# MS_8ADCPWM.net
KiCad netlist of a schematic drawn in EAGLE
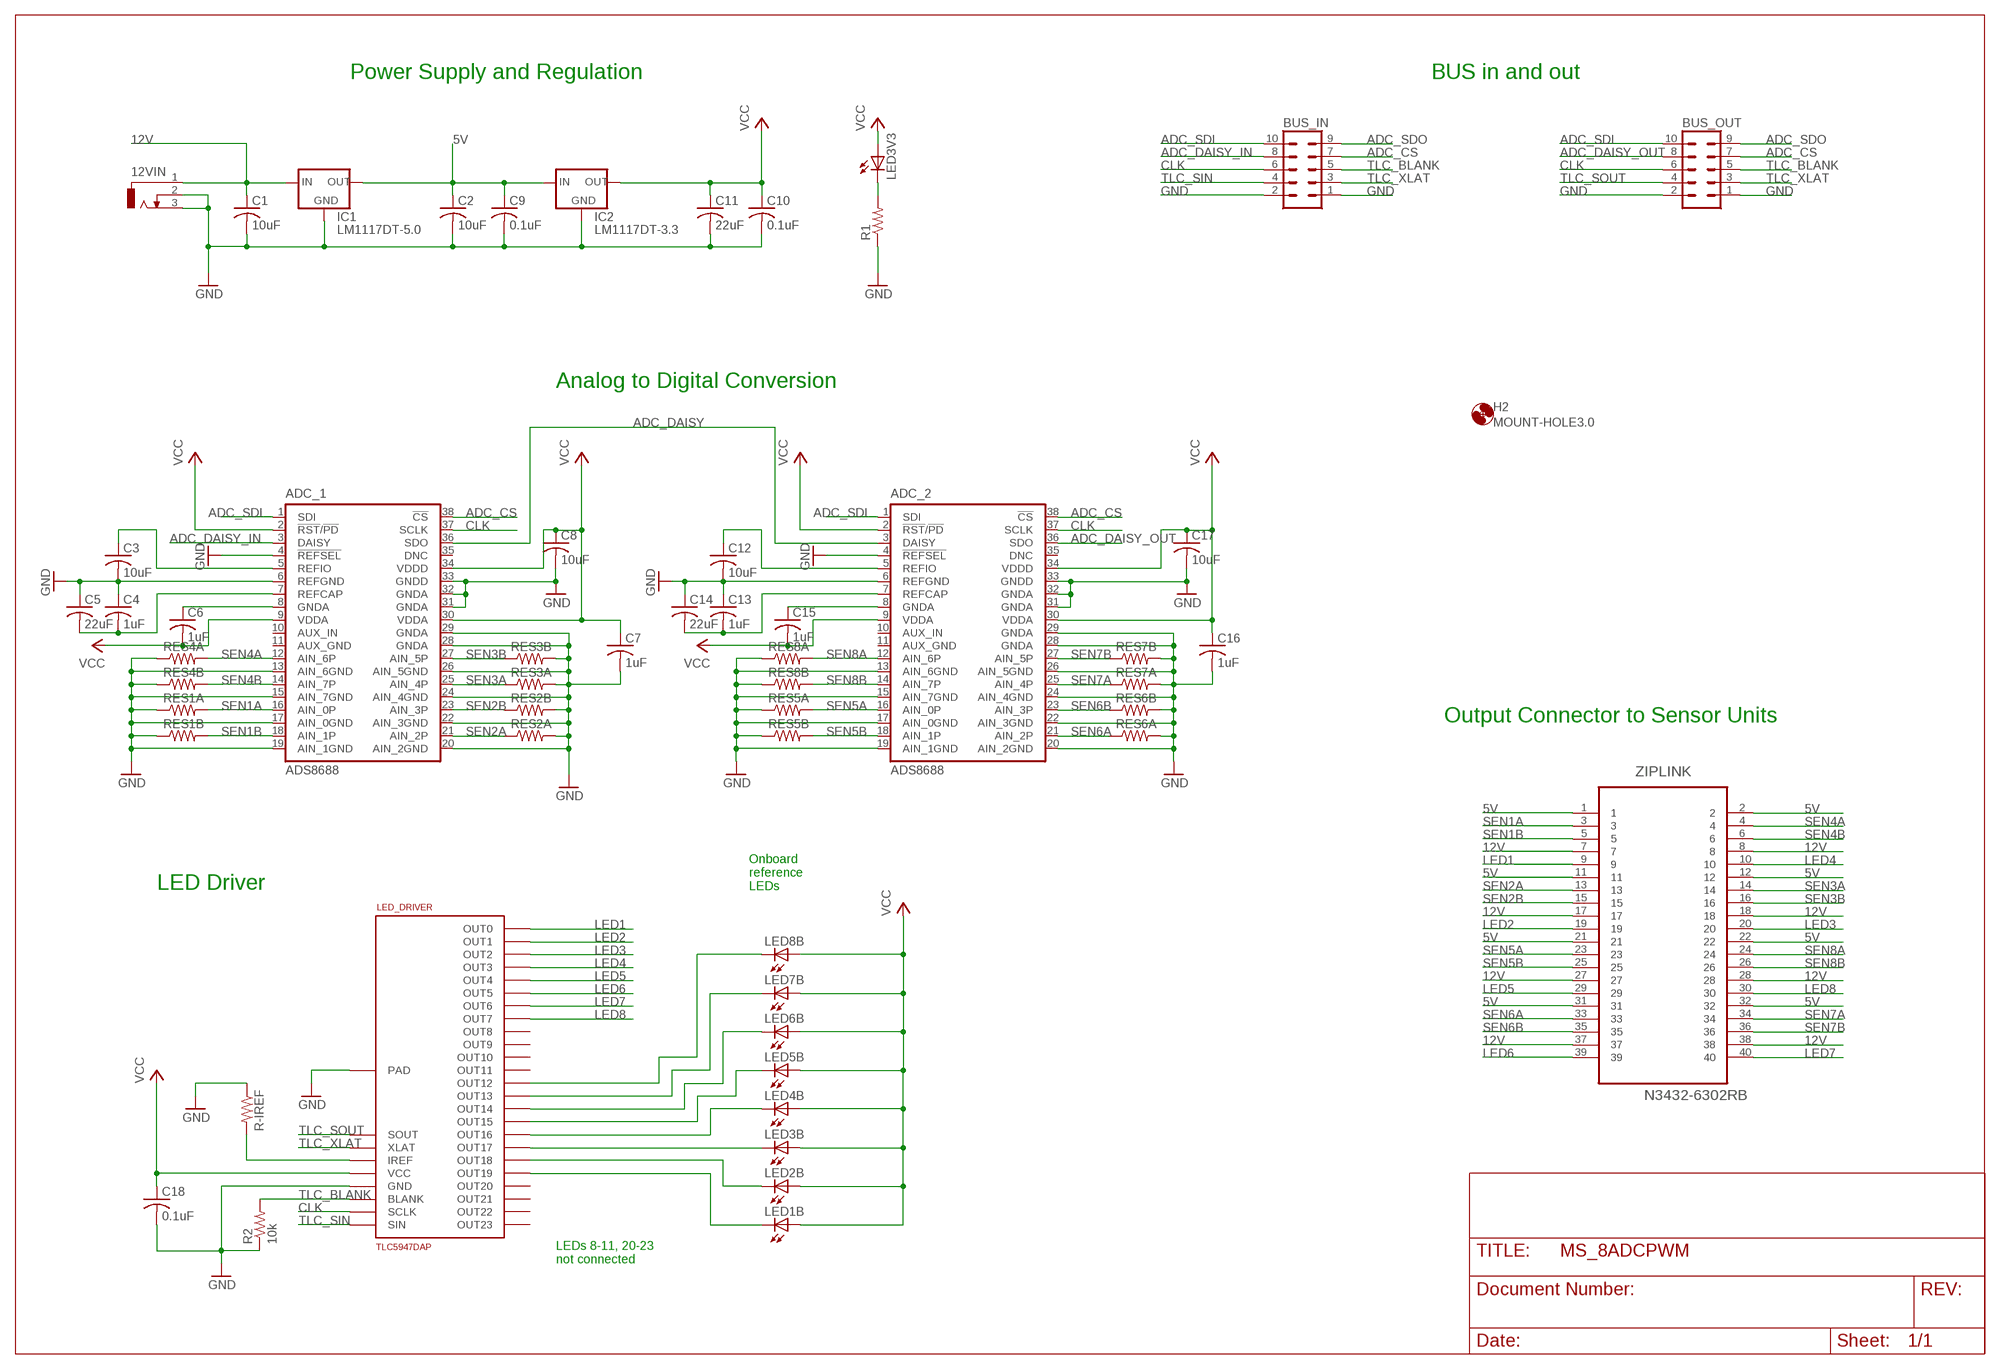
[diagram p0: schematic, sheet 1]

(export (version "E")
  (design (tool "Eeschema 10.0.6"))
  (components
    (comp (ref "12VIN")
      (value "DCJ0303")
      (footprint "eagle-import:DCJ0303")
      (libsource (lib "eagle-import") (part "DCJ0303"))
    )
    (comp (ref "ADC_1")
      (value "ADS8688")
      (footprint "eagle-import:DBT_R-PDSO-G38")
      (libsource (lib "eagle-import") (part "ADS8688"))
    )
    (comp (ref "ADC_2")
      (value "ADS8688")
      (footprint "eagle-import:DBT_R-PDSO-G38")
      (libsource (lib "eagle-import") (part "ADS8688"))
    )
    (comp (ref "BUS_IN")
      (value "ML10")
      (footprint "eagle-import:ML10")
      (libsource (lib "eagle-import") (part "ML10"))
    )
    (comp (ref "BUS_OUT")
      (value "ML10")
      (footprint "eagle-import:ML10")
      (libsource (lib "eagle-import") (part "ML10"))
    )
    (comp (ref "C1")
      (value "10uF")
      (footprint "eagle-import:C0805")
      (libsource (lib "eagle-import") (part "C-USC0805"))
    )
    (comp (ref "C2")
      (value "10uF")
      (footprint "eagle-import:C0805")
      (libsource (lib "eagle-import") (part "C-USC0805"))
    )
    (comp (ref "C3")
      (value "10uF")
      (footprint "eagle-import:C0805")
      (libsource (lib "eagle-import") (part "C-USC0805"))
    )
    (comp (ref "C4")
      (value "1uF")
      (footprint "eagle-import:C0805")
      (libsource (lib "eagle-import") (part "C-USC0805"))
    )
    (comp (ref "C5")
      (value "22uF")
      (footprint "eagle-import:C0805")
      (libsource (lib "eagle-import") (part "C-USC0805"))
    )
    (comp (ref "C6")
      (value "1uF")
      (footprint "eagle-import:C0805")
      (libsource (lib "eagle-import") (part "C-USC0805"))
    )
    (comp (ref "C7")
      (value "1uF")
      (footprint "eagle-import:C0805")
      (libsource (lib "eagle-import") (part "C-USC0805"))
    )
    (comp (ref "C8")
      (value "10uF")
      (footprint "eagle-import:C0805")
      (libsource (lib "eagle-import") (part "C-USC0805"))
    )
    (comp (ref "C9")
      (value "0.1uF")
      (footprint "eagle-import:C0805")
      (libsource (lib "eagle-import") (part "C-USC0805"))
    )
    (comp (ref "C10")
      (value "0.1uF")
      (footprint "eagle-import:C0805")
      (libsource (lib "eagle-import") (part "C-USC0805"))
    )
    (comp (ref "C11")
      (value "22uF")
      (footprint "eagle-import:C0805")
      (libsource (lib "eagle-import") (part "C-USC0805"))
    )
    (comp (ref "C12")
      (value "10uF")
      (footprint "eagle-import:C0805")
      (libsource (lib "eagle-import") (part "C-USC0805"))
    )
    (comp (ref "C13")
      (value "1uF")
      (footprint "eagle-import:C0805")
      (libsource (lib "eagle-import") (part "C-USC0805"))
    )
    (comp (ref "C14")
      (value "22uF")
      (footprint "eagle-import:C0805")
      (libsource (lib "eagle-import") (part "C-USC0805"))
    )
    (comp (ref "C15")
      (value "1uF")
      (footprint "eagle-import:C0805")
      (libsource (lib "eagle-import") (part "C-USC0805"))
    )
    (comp (ref "C16")
      (value "1uF")
      (footprint "eagle-import:C0805")
      (libsource (lib "eagle-import") (part "C-USC0805"))
    )
    (comp (ref "C17")
      (value "10uF")
      (footprint "eagle-import:C0805")
      (libsource (lib "eagle-import") (part "C-USC0805"))
    )
    (comp (ref "C18")
      (value "0.1uF")
      (footprint "eagle-import:C0805")
      (libsource (lib "eagle-import") (part "C-USC0805"))
    )
    (comp (ref "H2")
      (value "MOUNT-HOLE3.0")
      (footprint "eagle-import:3,0")
      (libsource (lib "eagle-import") (part "MOUNT-HOLE3.0"))
    )
    (comp (ref "IC1")
      (value "LM1117DT-5.0")
      (footprint "eagle-import:TO252")
      (fields (field (name "MF") "Texas Instruments"))
      (libsource (lib "eagle-import") (part "LM1117?-DT5.0"))
    )
    (comp (ref "IC2")
      (value "LM1117DT-3.3")
      (footprint "eagle-import:TO252")
      (fields (field (name "MF") "Texas Instruments"))
      (libsource (lib "eagle-import") (part "LM1117?-DT3.3"))
    )
    (comp (ref "LED1B")
      (value "LEDSMD2PLCC")
      (footprint "eagle-import:2-PLCC")
      (libsource (lib "eagle-import") (part "LEDSMD2PLCC"))
    )
    (comp (ref "LED2B")
      (value "LEDSMD2PLCC")
      (footprint "eagle-import:2-PLCC")
      (libsource (lib "eagle-import") (part "LEDSMD2PLCC"))
    )
    (comp (ref "LED3B")
      (value "LEDSMD2PLCC")
      (footprint "eagle-import:2-PLCC")
      (libsource (lib "eagle-import") (part "LEDSMD2PLCC"))
    )
    (comp (ref "LED3V3")
      (value "LEDCHIPLED_0805")
      (footprint "eagle-import:CHIPLED_0805")
      (libsource (lib "eagle-import") (part "LEDCHIPLED_0805"))
    )
    (comp (ref "LED4B")
      (value "LEDSMD2PLCC")
      (footprint "eagle-import:2-PLCC")
      (libsource (lib "eagle-import") (part "LEDSMD2PLCC"))
    )
    (comp (ref "LED5B")
      (value "LEDSMD2PLCC")
      (footprint "eagle-import:2-PLCC")
      (libsource (lib "eagle-import") (part "LEDSMD2PLCC"))
    )
    (comp (ref "LED6B")
      (value "LEDSMD2PLCC")
      (footprint "eagle-import:2-PLCC")
      (libsource (lib "eagle-import") (part "LEDSMD2PLCC"))
    )
    (comp (ref "LED7B")
      (value "LEDSMD2PLCC")
      (footprint "eagle-import:2-PLCC")
      (libsource (lib "eagle-import") (part "LEDSMD2PLCC"))
    )
    (comp (ref "LED8B")
      (value "LEDSMD2PLCC")
      (footprint "eagle-import:2-PLCC")
      (libsource (lib "eagle-import") (part "LEDSMD2PLCC"))
    )
    (comp (ref "LED_DRIVER")
      (value "TLC5947DAP")
      (footprint "eagle-import:HTSSOP32DAP")
      (libsource (lib "eagle-import") (part "TLC5947DAP"))
    )
    (comp (ref "R-IREF")
      (value "R-US_R1206")
      (footprint "eagle-import:R1206")
      (libsource (lib "eagle-import") (part "R-US_R1206"))
    )
    (comp (ref "R1")
      (value "R-US_R0805")
      (footprint "eagle-import:R0805")
      (libsource (lib "eagle-import") (part "R-US_R0805"))
    )
    (comp (ref "R2")
      (value "10k")
      (footprint "eagle-import:R1206")
      (libsource (lib "eagle-import") (part "R-US_R1206"))
    )
    (comp (ref "RES1A")
      (value "R-US_R1206")
      (footprint "eagle-import:R1206")
      (libsource (lib "eagle-import") (part "R-US_R1206"))
    )
    (comp (ref "RES1B")
      (value "R-US_R1206")
      (footprint "eagle-import:R1206")
      (libsource (lib "eagle-import") (part "R-US_R1206"))
    )
    (comp (ref "RES2A")
      (value "R-US_R1206")
      (footprint "eagle-import:R1206")
      (libsource (lib "eagle-import") (part "R-US_R1206"))
    )
    (comp (ref "RES2B")
      (value "R-US_R1206")
      (footprint "eagle-import:R1206")
      (libsource (lib "eagle-import") (part "R-US_R1206"))
    )
    (comp (ref "RES3A")
      (value "R-US_R1206")
      (footprint "eagle-import:R1206")
      (libsource (lib "eagle-import") (part "R-US_R1206"))
    )
    (comp (ref "RES3B")
      (value "R-US_R1206")
      (footprint "eagle-import:R1206")
      (libsource (lib "eagle-import") (part "R-US_R1206"))
    )
    (comp (ref "RES4A")
      (value "R-US_R1206")
      (footprint "eagle-import:R1206")
      (libsource (lib "eagle-import") (part "R-US_R1206"))
    )
    (comp (ref "RES4B")
      (value "R-US_R1206")
      (footprint "eagle-import:R1206")
      (libsource (lib "eagle-import") (part "R-US_R1206"))
    )
    (comp (ref "RES5A")
      (value "R-US_R1206")
      (footprint "eagle-import:R1206")
      (libsource (lib "eagle-import") (part "R-US_R1206"))
    )
    (comp (ref "RES5B")
      (value "R-US_R1206")
      (footprint "eagle-import:R1206")
      (libsource (lib "eagle-import") (part "R-US_R1206"))
    )
    (comp (ref "RES6A")
      (value "R-US_R1206")
      (footprint "eagle-import:R1206")
      (libsource (lib "eagle-import") (part "R-US_R1206"))
    )
    (comp (ref "RES6B")
      (value "R-US_R1206")
      (footprint "eagle-import:R1206")
      (libsource (lib "eagle-import") (part "R-US_R1206"))
    )
    (comp (ref "RES7A")
      (value "R-US_R1206")
      (footprint "eagle-import:R1206")
      (libsource (lib "eagle-import") (part "R-US_R1206"))
    )
    (comp (ref "RES7B")
      (value "R-US_R1206")
      (footprint "eagle-import:R1206")
      (libsource (lib "eagle-import") (part "R-US_R1206"))
    )
    (comp (ref "RES8A")
      (value "R-US_R1206")
      (footprint "eagle-import:R1206")
      (libsource (lib "eagle-import") (part "R-US_R1206"))
    )
    (comp (ref "RES8B")
      (value "R-US_R1206")
      (footprint "eagle-import:R1206")
      (libsource (lib "eagle-import") (part "R-US_R1206"))
    )
    (comp (ref "ZIPLINK")
      (value "N3432-6302RB")
      (footprint "eagle-import:3M_N3432-6302RB")
      (fields (field (name "MF") "3M"))
      (libsource (lib "eagle-import") (part "N3432-6302RB"))
    )
  )
  (nets
    (net (code "1") (name "/5V") (class "Default")
      (node (ref "C2") (pin "1") (pinfunction "1_1") (pintype "passive"))
      (node (ref "C9") (pin "1") (pinfunction "1_1") (pintype "passive"))
      (node (ref "IC1") (pin "3") (pinfunction "OUT_3") (pintype "passive"))
      (node (ref "IC2") (pin "2") (pinfunction "IN_2") (pintype "input"))
      (node (ref "ZIPLINK") (pin "1") (pinfunction "1_1") (pintype "passive"))
      (node (ref "ZIPLINK") (pin "11") (pinfunction "11_11") (pintype "passive"))
      (node (ref "ZIPLINK") (pin "12") (pinfunction "12_12") (pintype "passive"))
      (node (ref "ZIPLINK") (pin "2") (pinfunction "2_2") (pintype "passive"))
      (node (ref "ZIPLINK") (pin "21") (pinfunction "21_21") (pintype "passive"))
      (node (ref "ZIPLINK") (pin "22") (pinfunction "22_22") (pintype "passive"))
      (node (ref "ZIPLINK") (pin "31") (pinfunction "31_31") (pintype "passive"))
      (node (ref "ZIPLINK") (pin "32") (pinfunction "32_32") (pintype "passive"))
    )
    (net (code "2") (name "/12V") (class "Default")
      (node (ref "12VIN") (pin "1") (pinfunction "1_1") (pintype "passive"))
      (node (ref "C1") (pin "1") (pinfunction "1_1") (pintype "passive"))
      (node (ref "IC1") (pin "2") (pinfunction "IN_2") (pintype "input"))
      (node (ref "ZIPLINK") (pin "17") (pinfunction "17_17") (pintype "passive"))
      (node (ref "ZIPLINK") (pin "18") (pinfunction "18_18") (pintype "passive"))
      (node (ref "ZIPLINK") (pin "27") (pinfunction "27_27") (pintype "passive"))
      (node (ref "ZIPLINK") (pin "28") (pinfunction "28_28") (pintype "passive"))
      (node (ref "ZIPLINK") (pin "37") (pinfunction "37_37") (pintype "passive"))
      (node (ref "ZIPLINK") (pin "38") (pinfunction "38_38") (pintype "passive"))
      (node (ref "ZIPLINK") (pin "7") (pinfunction "7_7") (pintype "passive"))
      (node (ref "ZIPLINK") (pin "8") (pinfunction "8_8") (pintype "passive"))
    )
    (net (code "3") (name "/ADC_CS") (class "Default")
      (node (ref "ADC_1") (pin "38") (pinfunction "~{CS}_38") (pintype "input"))
      (node (ref "ADC_2") (pin "38") (pinfunction "~{CS}_38") (pintype "input"))
      (node (ref "BUS_IN") (pin "7") (pinfunction "7_7") (pintype "passive"))
      (node (ref "BUS_OUT") (pin "7") (pinfunction "7_7") (pintype "passive"))
    )
    (net (code "4") (name "/ADC_DAISY") (class "Default")
      (node (ref "ADC_1") (pin "36") (pinfunction "SDO_36") (pintype "bidirectional"))
      (node (ref "ADC_2") (pin "3") (pinfunction "DAISY_3") (pintype "input"))
    )
    (net (code "5") (name "/ADC_DAISY_IN") (class "Default")
      (node (ref "ADC_1") (pin "3") (pinfunction "DAISY_3") (pintype "input"))
      (node (ref "BUS_IN") (pin "8") (pinfunction "8_8") (pintype "passive"))
    )
    (net (code "6") (name "/ADC_DAISY_OUT") (class "Default")
      (node (ref "ADC_2") (pin "36") (pinfunction "SDO_36") (pintype "bidirectional"))
      (node (ref "BUS_OUT") (pin "8") (pinfunction "8_8") (pintype "passive"))
    )
    (net (code "7") (name "/ADC_SDI") (class "Default")
      (node (ref "ADC_1") (pin "1") (pinfunction "SDI_1") (pintype "input"))
      (node (ref "ADC_2") (pin "1") (pinfunction "SDI_1") (pintype "input"))
      (node (ref "BUS_IN") (pin "10") (pinfunction "10_10") (pintype "passive"))
      (node (ref "BUS_OUT") (pin "10") (pinfunction "10_10") (pintype "passive"))
    )
    (net (code "8") (name "/ADC_SDO") (class "Default")
      (node (ref "BUS_IN") (pin "9") (pinfunction "9_9") (pintype "passive"))
      (node (ref "BUS_OUT") (pin "9") (pinfunction "9_9") (pintype "passive"))
    )
    (net (code "9") (name "/CLK") (class "Default")
      (node (ref "ADC_1") (pin "37") (pinfunction "SCLK_37") (pintype "input"))
      (node (ref "ADC_2") (pin "37") (pinfunction "SCLK_37") (pintype "input"))
      (node (ref "BUS_IN") (pin "6") (pinfunction "6_6") (pintype "passive"))
      (node (ref "BUS_OUT") (pin "6") (pinfunction "6_6") (pintype "passive"))
      (node (ref "LED_DRIVER") (pin "3") (pinfunction "SCLK_3") (pintype "bidirectional"))
    )
    (net (code "10") (name "/LED1") (class "Default")
      (node (ref "LED_DRIVER") (pin "5") (pinfunction "OUT0_5") (pintype "bidirectional"))
      (node (ref "ZIPLINK") (pin "9") (pinfunction "9_9") (pintype "passive"))
    )
    (net (code "11") (name "/LED2") (class "Default")
      (node (ref "LED_DRIVER") (pin "6") (pinfunction "OUT1_6") (pintype "bidirectional"))
      (node (ref "ZIPLINK") (pin "19") (pinfunction "19_19") (pintype "passive"))
    )
    (net (code "12") (name "/LED3") (class "Default")
      (node (ref "LED_DRIVER") (pin "7") (pinfunction "OUT2_7") (pintype "bidirectional"))
      (node (ref "ZIPLINK") (pin "20") (pinfunction "20_20") (pintype "passive"))
    )
    (net (code "13") (name "/LED4") (class "Default")
      (node (ref "LED_DRIVER") (pin "8") (pinfunction "OUT3_8") (pintype "bidirectional"))
      (node (ref "ZIPLINK") (pin "10") (pinfunction "10_10") (pintype "passive"))
    )
    (net (code "14") (name "/LED5") (class "Default")
      (node (ref "LED_DRIVER") (pin "9") (pinfunction "OUT4_9") (pintype "bidirectional"))
      (node (ref "ZIPLINK") (pin "29") (pinfunction "29_29") (pintype "passive"))
    )
    (net (code "15") (name "/LED6") (class "Default")
      (node (ref "LED_DRIVER") (pin "10") (pinfunction "OUT5_10") (pintype "bidirectional"))
      (node (ref "ZIPLINK") (pin "39") (pinfunction "39_39") (pintype "passive"))
    )
    (net (code "16") (name "/LED7") (class "Default")
      (node (ref "LED_DRIVER") (pin "11") (pinfunction "OUT6_11") (pintype "bidirectional"))
      (node (ref "ZIPLINK") (pin "40") (pinfunction "40_40") (pintype "passive"))
    )
    (net (code "17") (name "/LED8") (class "Default")
      (node (ref "LED_DRIVER") (pin "12") (pinfunction "OUT7_12") (pintype "bidirectional"))
      (node (ref "ZIPLINK") (pin "30") (pinfunction "30_30") (pintype "passive"))
    )
    (net (code "18") (name "/SEN1A") (class "Default")
      (node (ref "ADC_1") (pin "16") (pinfunction "AIN_0P_16") (pintype "input"))
      (node (ref "RES1A") (pin "2") (pinfunction "2_2") (pintype "passive"))
      (node (ref "ZIPLINK") (pin "3") (pinfunction "3_3") (pintype "passive"))
    )
    (net (code "19") (name "/SEN1B") (class "Default")
      (node (ref "ADC_1") (pin "18") (pinfunction "AIN_1P_18") (pintype "input"))
      (node (ref "RES1B") (pin "2") (pinfunction "2_2") (pintype "passive"))
      (node (ref "ZIPLINK") (pin "5") (pinfunction "5_5") (pintype "passive"))
    )
    (net (code "20") (name "/SEN2A") (class "Default")
      (node (ref "ADC_1") (pin "21") (pinfunction "AIN_2P_21") (pintype "input"))
      (node (ref "RES2A") (pin "1") (pinfunction "1_1") (pintype "passive"))
      (node (ref "ZIPLINK") (pin "13") (pinfunction "13_13") (pintype "passive"))
    )
    (net (code "21") (name "/SEN2B") (class "Default")
      (node (ref "ADC_1") (pin "23") (pinfunction "AIN_3P_23") (pintype "input"))
      (node (ref "RES2B") (pin "1") (pinfunction "1_1") (pintype "passive"))
      (node (ref "ZIPLINK") (pin "15") (pinfunction "15_15") (pintype "passive"))
    )
    (net (code "22") (name "/SEN3A") (class "Default")
      (node (ref "ADC_1") (pin "25") (pinfunction "AIN_4P_25") (pintype "input"))
      (node (ref "RES3A") (pin "1") (pinfunction "1_1") (pintype "passive"))
      (node (ref "ZIPLINK") (pin "14") (pinfunction "14_14") (pintype "passive"))
    )
    (net (code "23") (name "/SEN3B") (class "Default")
      (node (ref "ADC_1") (pin "27") (pinfunction "AIN_5P_27") (pintype "input"))
      (node (ref "RES3B") (pin "1") (pinfunction "1_1") (pintype "passive"))
      (node (ref "ZIPLINK") (pin "16") (pinfunction "16_16") (pintype "passive"))
    )
    (net (code "24") (name "/SEN4A") (class "Default")
      (node (ref "ADC_1") (pin "12") (pinfunction "AIN_6P_12") (pintype "input"))
      (node (ref "RES4A") (pin "2") (pinfunction "2_2") (pintype "passive"))
      (node (ref "ZIPLINK") (pin "4") (pinfunction "4_4") (pintype "passive"))
    )
    (net (code "25") (name "/SEN4B") (class "Default")
      (node (ref "ADC_1") (pin "14") (pinfunction "AIN_7P_14") (pintype "input"))
      (node (ref "RES4B") (pin "2") (pinfunction "2_2") (pintype "passive"))
      (node (ref "ZIPLINK") (pin "6") (pinfunction "6_6") (pintype "passive"))
    )
    (net (code "26") (name "/SEN5A") (class "Default")
      (node (ref "ADC_2") (pin "16") (pinfunction "AIN_0P_16") (pintype "input"))
      (node (ref "RES5A") (pin "2") (pinfunction "2_2") (pintype "passive"))
      (node (ref "ZIPLINK") (pin "23") (pinfunction "23_23") (pintype "passive"))
    )
    (net (code "27") (name "/SEN5B") (class "Default")
      (node (ref "ADC_2") (pin "18") (pinfunction "AIN_1P_18") (pintype "input"))
      (node (ref "RES5B") (pin "2") (pinfunction "2_2") (pintype "passive"))
      (node (ref "ZIPLINK") (pin "25") (pinfunction "25_25") (pintype "passive"))
    )
    (net (code "28") (name "/SEN6A") (class "Default")
      (node (ref "ADC_2") (pin "21") (pinfunction "AIN_2P_21") (pintype "input"))
      (node (ref "RES6A") (pin "1") (pinfunction "1_1") (pintype "passive"))
      (node (ref "ZIPLINK") (pin "33") (pinfunction "33_33") (pintype "passive"))
    )
    (net (code "29") (name "/SEN6B") (class "Default")
      (node (ref "ADC_2") (pin "23") (pinfunction "AIN_3P_23") (pintype "input"))
      (node (ref "RES6B") (pin "1") (pinfunction "1_1") (pintype "passive"))
      (node (ref "ZIPLINK") (pin "35") (pinfunction "35_35") (pintype "passive"))
    )
    (net (code "30") (name "/SEN7A") (class "Default")
      (node (ref "ADC_2") (pin "25") (pinfunction "AIN_4P_25") (pintype "input"))
      (node (ref "RES7A") (pin "1") (pinfunction "1_1") (pintype "passive"))
      (node (ref "ZIPLINK") (pin "34") (pinfunction "34_34") (pintype "passive"))
    )
    (net (code "31") (name "/SEN7B") (class "Default")
      (node (ref "ADC_2") (pin "27") (pinfunction "AIN_5P_27") (pintype "input"))
      (node (ref "RES7B") (pin "1") (pinfunction "1_1") (pintype "passive"))
      (node (ref "ZIPLINK") (pin "36") (pinfunction "36_36") (pintype "passive"))
    )
    (net (code "32") (name "/SEN8A") (class "Default")
      (node (ref "ADC_2") (pin "12") (pinfunction "AIN_6P_12") (pintype "input"))
      (node (ref "RES8A") (pin "2") (pinfunction "2_2") (pintype "passive"))
      (node (ref "ZIPLINK") (pin "24") (pinfunction "24_24") (pintype "passive"))
    )
    (net (code "33") (name "/SEN8B") (class "Default")
      (node (ref "ADC_2") (pin "14") (pinfunction "AIN_7P_14") (pintype "input"))
      (node (ref "RES8B") (pin "2") (pinfunction "2_2") (pintype "passive"))
      (node (ref "ZIPLINK") (pin "26") (pinfunction "26_26") (pintype "passive"))
    )
    (net (code "34") (name "/TLC_BLANK") (class "Default")
      (node (ref "BUS_IN") (pin "5") (pinfunction "5_5") (pintype "passive"))
      (node (ref "BUS_OUT") (pin "5") (pinfunction "5_5") (pintype "passive"))
      (node (ref "LED_DRIVER") (pin "2") (pinfunction "BLANK_2") (pintype "bidirectional"))
      (node (ref "R2") (pin "2") (pinfunction "2_2") (pintype "passive"))
    )
    (net (code "35") (name "/TLC_SIN") (class "Default")
      (node (ref "BUS_IN") (pin "4") (pinfunction "4_4") (pintype "passive"))
      (node (ref "LED_DRIVER") (pin "4") (pinfunction "SIN_4") (pintype "bidirectional"))
    )
    (net (code "36") (name "/TLC_SOUT") (class "Default")
      (node (ref "BUS_OUT") (pin "4") (pinfunction "4_4") (pintype "passive"))
      (node (ref "LED_DRIVER") (pin "29") (pinfunction "SOUT_29") (pintype "bidirectional"))
    )
    (net (code "37") (name "/TLC_XLAT") (class "Default")
      (node (ref "BUS_IN") (pin "3") (pinfunction "3_3") (pintype "passive"))
      (node (ref "BUS_OUT") (pin "3") (pinfunction "3_3") (pintype "passive"))
      (node (ref "LED_DRIVER") (pin "30") (pinfunction "XLAT_30") (pintype "bidirectional"))
    )
    (net (code "38") (name "GND") (class "Default")
      (node (ref "12VIN") (pin "2") (pinfunction "2_2") (pintype "passive"))
      (node (ref "12VIN") (pin "3") (pinfunction "3_3") (pintype "passive"))
      (node (ref "ADC_1") (pin "13") (pinfunction "AIN_6GND_13") (pintype "input"))
      (node (ref "ADC_1") (pin "15") (pinfunction "AIN_7GND_15") (pintype "input"))
      (node (ref "ADC_1") (pin "17") (pinfunction "AIN_0GND_17") (pintype "input"))
      (node (ref "ADC_1") (pin "19") (pinfunction "AIN_1GND_19") (pintype "input"))
      (node (ref "ADC_1") (pin "20") (pinfunction "AIN_2GND_20") (pintype "input"))
      (node (ref "ADC_1") (pin "22") (pinfunction "AIN_3GND_22") (pintype "input"))
      (node (ref "ADC_1") (pin "24") (pinfunction "AIN_4GND_24") (pintype "input"))
      (node (ref "ADC_1") (pin "26") (pinfunction "AIN_5GND_26") (pintype "input"))
      (node (ref "ADC_1") (pin "28") (pinfunction "GNDA_28") (pintype "power_in"))
      (node (ref "ADC_1") (pin "29") (pinfunction "GNDA_29") (pintype "power_in"))
      (node (ref "ADC_1") (pin "31") (pinfunction "GNDA_31") (pintype "power_in"))
      (node (ref "ADC_1") (pin "32") (pinfunction "GNDA_32") (pintype "power_in"))
      (node (ref "ADC_1") (pin "33") (pinfunction "GNDD_33") (pintype "power_in"))
      (node (ref "ADC_1") (pin "4") (pinfunction "~{REFSEL}_4") (pintype "input"))
      (node (ref "ADC_1") (pin "6") (pinfunction "REFGND_6") (pintype "power_in"))
      (node (ref "ADC_2") (pin "13") (pinfunction "AIN_6GND_13") (pintype "input"))
      (node (ref "ADC_2") (pin "15") (pinfunction "AIN_7GND_15") (pintype "input"))
      (node (ref "ADC_2") (pin "17") (pinfunction "AIN_0GND_17") (pintype "input"))
      (node (ref "ADC_2") (pin "19") (pinfunction "AIN_1GND_19") (pintype "input"))
      (node (ref "ADC_2") (pin "20") (pinfunction "AIN_2GND_20") (pintype "input"))
      (node (ref "ADC_2") (pin "22") (pinfunction "AIN_3GND_22") (pintype "input"))
      (node (ref "ADC_2") (pin "24") (pinfunction "AIN_4GND_24") (pintype "input"))
      (node (ref "ADC_2") (pin "26") (pinfunction "AIN_5GND_26") (pintype "input"))
      (node (ref "ADC_2") (pin "28") (pinfunction "GNDA_28") (pintype "power_in"))
      (node (ref "ADC_2") (pin "29") (pinfunction "GNDA_29") (pintype "power_in"))
      (node (ref "ADC_2") (pin "31") (pinfunction "GNDA_31") (pintype "power_in"))
      (node (ref "ADC_2") (pin "32") (pinfunction "GNDA_32") (pintype "power_in"))
      (node (ref "ADC_2") (pin "33") (pinfunction "GNDD_33") (pintype "power_in"))
      (node (ref "ADC_2") (pin "4") (pinfunction "~{REFSEL}_4") (pintype "input"))
      (node (ref "ADC_2") (pin "6") (pinfunction "REFGND_6") (pintype "power_in"))
      (node (ref "BUS_IN") (pin "1") (pinfunction "1_1") (pintype "passive"))
      (node (ref "BUS_IN") (pin "2") (pinfunction "2_2") (pintype "passive"))
      (node (ref "BUS_OUT") (pin "1") (pinfunction "1_1") (pintype "passive"))
      (node (ref "BUS_OUT") (pin "2") (pinfunction "2_2") (pintype "passive"))
      (node (ref "C1") (pin "2") (pinfunction "2_2") (pintype "passive"))
      (node (ref "C10") (pin "2") (pinfunction "2_2") (pintype "passive"))
      (node (ref "C11") (pin "2") (pinfunction "2_2") (pintype "passive"))
      (node (ref "C12") (pin "2") (pinfunction "2_2") (pintype "passive"))
      (node (ref "C13") (pin "1") (pinfunction "1_1") (pintype "passive"))
      (node (ref "C14") (pin "1") (pinfunction "1_1") (pintype "passive"))
      (node (ref "C16") (pin "2") (pinfunction "2_2") (pintype "passive"))
      (node (ref "C17") (pin "2") (pinfunction "2_2") (pintype "passive"))
      (node (ref "C18") (pin "2") (pinfunction "2_2") (pintype "passive"))
      (node (ref "C2") (pin "2") (pinfunction "2_2") (pintype "passive"))
      (node (ref "C3") (pin "2") (pinfunction "2_2") (pintype "passive"))
      (node (ref "C4") (pin "1") (pinfunction "1_1") (pintype "passive"))
      (node (ref "C5") (pin "1") (pinfunction "1_1") (pintype "passive"))
      (node (ref "C7") (pin "2") (pinfunction "2_2") (pintype "passive"))
      (node (ref "C8") (pin "2") (pinfunction "2_2") (pintype "passive"))
      (node (ref "C9") (pin "2") (pinfunction "2_2") (pintype "passive"))
      (node (ref "IC1") (pin "1") (pinfunction "GND_1") (pintype "input"))
      (node (ref "IC2") (pin "1") (pinfunction "GND_1") (pintype "input"))
      (node (ref "LED_DRIVER") (pin "1") (pinfunction "GND_1") (pintype "bidirectional"))
      (node (ref "LED_DRIVER") (pin "EXP") (pinfunction "PAD_EXP") (pintype "bidirectional"))
      (node (ref "R-IREF") (pin "1") (pinfunction "1_1") (pintype "passive"))
      (node (ref "R1") (pin "1") (pinfunction "1_1") (pintype "passive"))
      (node (ref "R2") (pin "1") (pinfunction "1_1") (pintype "passive"))
      (node (ref "RES1A") (pin "1") (pinfunction "1_1") (pintype "passive"))
      (node (ref "RES1B") (pin "1") (pinfunction "1_1") (pintype "passive"))
      (node (ref "RES2A") (pin "2") (pinfunction "2_2") (pintype "passive"))
      (node (ref "RES2B") (pin "2") (pinfunction "2_2") (pintype "passive"))
      (node (ref "RES3A") (pin "2") (pinfunction "2_2") (pintype "passive"))
      (node (ref "RES3B") (pin "2") (pinfunction "2_2") (pintype "passive"))
      (node (ref "RES4A") (pin "1") (pinfunction "1_1") (pintype "passive"))
      (node (ref "RES4B") (pin "1") (pinfunction "1_1") (pintype "passive"))
      (node (ref "RES5A") (pin "1") (pinfunction "1_1") (pintype "passive"))
      (node (ref "RES5B") (pin "1") (pinfunction "1_1") (pintype "passive"))
      (node (ref "RES6A") (pin "2") (pinfunction "2_2") (pintype "passive"))
      (node (ref "RES6B") (pin "2") (pinfunction "2_2") (pintype "passive"))
      (node (ref "RES7A") (pin "2") (pinfunction "2_2") (pintype "passive"))
      (node (ref "RES7B") (pin "2") (pinfunction "2_2") (pintype "passive"))
      (node (ref "RES8A") (pin "1") (pinfunction "1_1") (pintype "passive"))
      (node (ref "RES8B") (pin "1") (pinfunction "1_1") (pintype "passive"))
    )
    (net (code "39") (name "Net-(ADC_1-GNDA-Pad8)") (class "Default")
      (node (ref "ADC_1") (pin "8") (pinfunction "GNDA_8") (pintype "power_in"))
      (node (ref "C6") (pin "1") (pinfunction "1_1") (pintype "passive"))
    )
    (net (code "40") (name "Net-(ADC_1-REFCAP)") (class "Default")
      (node (ref "ADC_1") (pin "7") (pinfunction "REFCAP_7") (pintype "output"))
      (node (ref "C4") (pin "2") (pinfunction "2_2") (pintype "passive"))
      (node (ref "C5") (pin "2") (pinfunction "2_2") (pintype "passive"))
    )
    (net (code "41") (name "Net-(ADC_1-REFIO)") (class "Default")
      (node (ref "ADC_1") (pin "5") (pinfunction "REFIO_5") (pintype "bidirectional"))
      (node (ref "C3") (pin "1") (pinfunction "1_1") (pintype "passive"))
    )
    (net (code "42") (name "Net-(ADC_2-GNDA-Pad8)") (class "Default")
      (node (ref "ADC_2") (pin "8") (pinfunction "GNDA_8") (pintype "power_in"))
      (node (ref "C15") (pin "1") (pinfunction "1_1") (pintype "passive"))
    )
    (net (code "43") (name "Net-(ADC_2-REFCAP)") (class "Default")
      (node (ref "ADC_2") (pin "7") (pinfunction "REFCAP_7") (pintype "output"))
      (node (ref "C13") (pin "2") (pinfunction "2_2") (pintype "passive"))
      (node (ref "C14") (pin "2") (pinfunction "2_2") (pintype "passive"))
    )
    (net (code "44") (name "Net-(ADC_2-REFIO)") (class "Default")
      (node (ref "ADC_2") (pin "5") (pinfunction "REFIO_5") (pintype "bidirectional"))
      (node (ref "C12") (pin "1") (pinfunction "1_1") (pintype "passive"))
    )
    (net (code "45") (name "Net-(LED3V3-PadC)") (class "Default")
      (node (ref "LED3V3") (pin "C") (pinfunction "C_C") (pintype "passive"))
      (node (ref "R1") (pin "2") (pinfunction "2_2") (pintype "passive"))
    )
    (net (code "46") (name "Net-(LED_DRIVER-IREF)") (class "Default")
      (node (ref "LED_DRIVER") (pin "31") (pinfunction "IREF_31") (pintype "bidirectional"))
      (node (ref "R-IREF") (pin "2") (pinfunction "2_2") (pintype "passive"))
    )
    (net (code "47") (name "Net-(LED_DRIVER-OUT12)") (class "Default")
      (node (ref "LED8B") (pin "C") (pinfunction "C_C") (pintype "passive"))
      (node (ref "LED_DRIVER") (pin "17") (pinfunction "OUT12_17") (pintype "bidirectional"))
    )
    (net (code "48") (name "Net-(LED_DRIVER-OUT13)") (class "Default")
      (node (ref "LED7B") (pin "C") (pinfunction "C_C") (pintype "passive"))
      (node (ref "LED_DRIVER") (pin "18") (pinfunction "OUT13_18") (pintype "bidirectional"))
    )
    (net (code "49") (name "Net-(LED_DRIVER-OUT14)") (class "Default")
      (node (ref "LED6B") (pin "C") (pinfunction "C_C") (pintype "passive"))
      (node (ref "LED_DRIVER") (pin "19") (pinfunction "OUT14_19") (pintype "bidirectional"))
    )
    (net (code "50") (name "Net-(LED_DRIVER-OUT15)") (class "Default")
      (node (ref "LED5B") (pin "C") (pinfunction "C_C") (pintype "passive"))
      (node (ref "LED_DRIVER") (pin "20") (pinfunction "OUT15_20") (pintype "bidirectional"))
    )
    (net (code "51") (name "Net-(LED_DRIVER-OUT16)") (class "Default")
      (node (ref "LED4B") (pin "C") (pinfunction "C_C") (pintype "passive"))
      (node (ref "LED_DRIVER") (pin "21") (pinfunction "OUT16_21") (pintype "bidirectional"))
    )
    (net (code "52") (name "Net-(LED_DRIVER-OUT17)") (class "Default")
      (node (ref "LED3B") (pin "C") (pinfunction "C_C") (pintype "passive"))
      (node (ref "LED_DRIVER") (pin "22") (pinfunction "OUT17_22") (pintype "bidirectional"))
    )
    (net (code "53") (name "Net-(LED_DRIVER-OUT18)") (class "Default")
      (node (ref "LED2B") (pin "C") (pinfunction "C_C") (pintype "passive"))
      (node (ref "LED_DRIVER") (pin "23") (pinfunction "OUT18_23") (pintype "bidirectional"))
    )
    (net (code "54") (name "Net-(LED_DRIVER-OUT19)") (class "Default")
      (node (ref "LED1B") (pin "C") (pinfunction "C_C") (pintype "passive"))
      (node (ref "LED_DRIVER") (pin "24") (pinfunction "OUT19_24") (pintype "bidirectional"))
    )
    (net (code "55") (name "VCC") (class "Default")
      (node (ref "ADC_1") (pin "2") (pinfunction "~{RST}/~{PD}_2") (pintype "input"))
      (node (ref "ADC_1") (pin "30") (pinfunction "VDDA_30") (pintype "power_in"))
      (node (ref "ADC_1") (pin "34") (pinfunction "VDDD_34") (pintype "power_in"))
      (node (ref "ADC_1") (pin "9") (pinfunction "VDDA_9") (pintype "power_in"))
      (node (ref "ADC_2") (pin "2") (pinfunction "~{RST}/~{PD}_2") (pintype "input"))
      (node (ref "ADC_2") (pin "30") (pinfunction "VDDA_30") (pintype "power_in"))
      (node (ref "ADC_2") (pin "34") (pinfunction "VDDD_34") (pintype "power_in"))
      (node (ref "ADC_2") (pin "9") (pinfunction "VDDA_9") (pintype "power_in"))
      (node (ref "C10") (pin "1") (pinfunction "1_1") (pintype "passive"))
      (node (ref "C11") (pin "1") (pinfunction "1_1") (pintype "passive"))
      (node (ref "C15") (pin "2") (pinfunction "2_2") (pintype "passive"))
      (node (ref "C16") (pin "1") (pinfunction "1_1") (pintype "passive"))
      (node (ref "C17") (pin "1") (pinfunction "1_1") (pintype "passive"))
      (node (ref "C18") (pin "1") (pinfunction "1_1") (pintype "passive"))
      (node (ref "C6") (pin "2") (pinfunction "2_2") (pintype "passive"))
      (node (ref "C7") (pin "1") (pinfunction "1_1") (pintype "passive"))
      (node (ref "C8") (pin "1") (pinfunction "1_1") (pintype "passive"))
      (node (ref "IC2") (pin "3") (pinfunction "OUT_3") (pintype "passive"))
      (node (ref "LED1B") (pin "A") (pinfunction "A_A") (pintype "passive"))
      (node (ref "LED2B") (pin "A") (pinfunction "A_A") (pintype "passive"))
      (node (ref "LED3B") (pin "A") (pinfunction "A_A") (pintype "passive"))
      (node (ref "LED3V3") (pin "A") (pinfunction "A_A") (pintype "passive"))
      (node (ref "LED4B") (pin "A") (pinfunction "A_A") (pintype "passive"))
      (node (ref "LED5B") (pin "A") (pinfunction "A_A") (pintype "passive"))
      (node (ref "LED6B") (pin "A") (pinfunction "A_A") (pintype "passive"))
      (node (ref "LED7B") (pin "A") (pinfunction "A_A") (pintype "passive"))
      (node (ref "LED8B") (pin "A") (pinfunction "A_A") (pintype "passive"))
      (node (ref "LED_DRIVER") (pin "32") (pinfunction "VCC_32") (pintype "bidirectional"))
    )
    (net (code "56") (name "unconnected-(ADC_1-AUX_GND-Pad11)") (class "Default")
      (node (ref "ADC_1") (pin "11") (pinfunction "AUX_GND_11") (pintype "input"))
    )
    (net (code "57") (name "unconnected-(ADC_1-AUX_IN-Pad10)") (class "Default")
      (node (ref "ADC_1") (pin "10") (pinfunction "AUX_IN_10") (pintype "input"))
    )
    (net (code "58") (name "unconnected-(ADC_1-DNC-Pad35)") (class "Default")
      (node (ref "ADC_1") (pin "35") (pinfunction "DNC_35") (pintype "no_connect"))
    )
    (net (code "59") (name "unconnected-(ADC_2-AUX_GND-Pad11)") (class "Default")
      (node (ref "ADC_2") (pin "11") (pinfunction "AUX_GND_11") (pintype "input"))
    )
    (net (code "60") (name "unconnected-(ADC_2-AUX_IN-Pad10)") (class "Default")
      (node (ref "ADC_2") (pin "10") (pinfunction "AUX_IN_10") (pintype "input"))
    )
    (net (code "61") (name "unconnected-(ADC_2-DNC-Pad35)") (class "Default")
      (node (ref "ADC_2") (pin "35") (pinfunction "DNC_35") (pintype "no_connect"))
    )
    (net (code "62") (name "unconnected-(LED_DRIVER-OUT8-Pad13)") (class "Default")
      (node (ref "LED_DRIVER") (pin "13") (pinfunction "OUT8_13") (pintype "bidirectional"))
    )
    (net (code "63") (name "unconnected-(LED_DRIVER-OUT9-Pad14)") (class "Default")
      (node (ref "LED_DRIVER") (pin "14") (pinfunction "OUT9_14") (pintype "bidirectional"))
    )
    (net (code "64") (name "unconnected-(LED_DRIVER-OUT10-Pad15)") (class "Default")
      (node (ref "LED_DRIVER") (pin "15") (pinfunction "OUT10_15") (pintype "bidirectional"))
    )
    (net (code "65") (name "unconnected-(LED_DRIVER-OUT11-Pad16)") (class "Default")
      (node (ref "LED_DRIVER") (pin "16") (pinfunction "OUT11_16") (pintype "bidirectional"))
    )
    (net (code "66") (name "unconnected-(LED_DRIVER-OUT20-Pad25)") (class "Default")
      (node (ref "LED_DRIVER") (pin "25") (pinfunction "OUT20_25") (pintype "bidirectional"))
    )
    (net (code "67") (name "unconnected-(LED_DRIVER-OUT21-Pad26)") (class "Default")
      (node (ref "LED_DRIVER") (pin "26") (pinfunction "OUT21_26") (pintype "bidirectional"))
    )
    (net (code "68") (name "unconnected-(LED_DRIVER-OUT22-Pad27)") (class "Default")
      (node (ref "LED_DRIVER") (pin "27") (pinfunction "OUT22_27") (pintype "bidirectional"))
    )
    (net (code "69") (name "unconnected-(LED_DRIVER-OUT23-Pad28)") (class "Default")
      (node (ref "LED_DRIVER") (pin "28") (pinfunction "OUT23_28") (pintype "bidirectional"))
    )
  )
)
